# audio_amp.net
KiCad netlist of a schematic drawn in Altium Designer
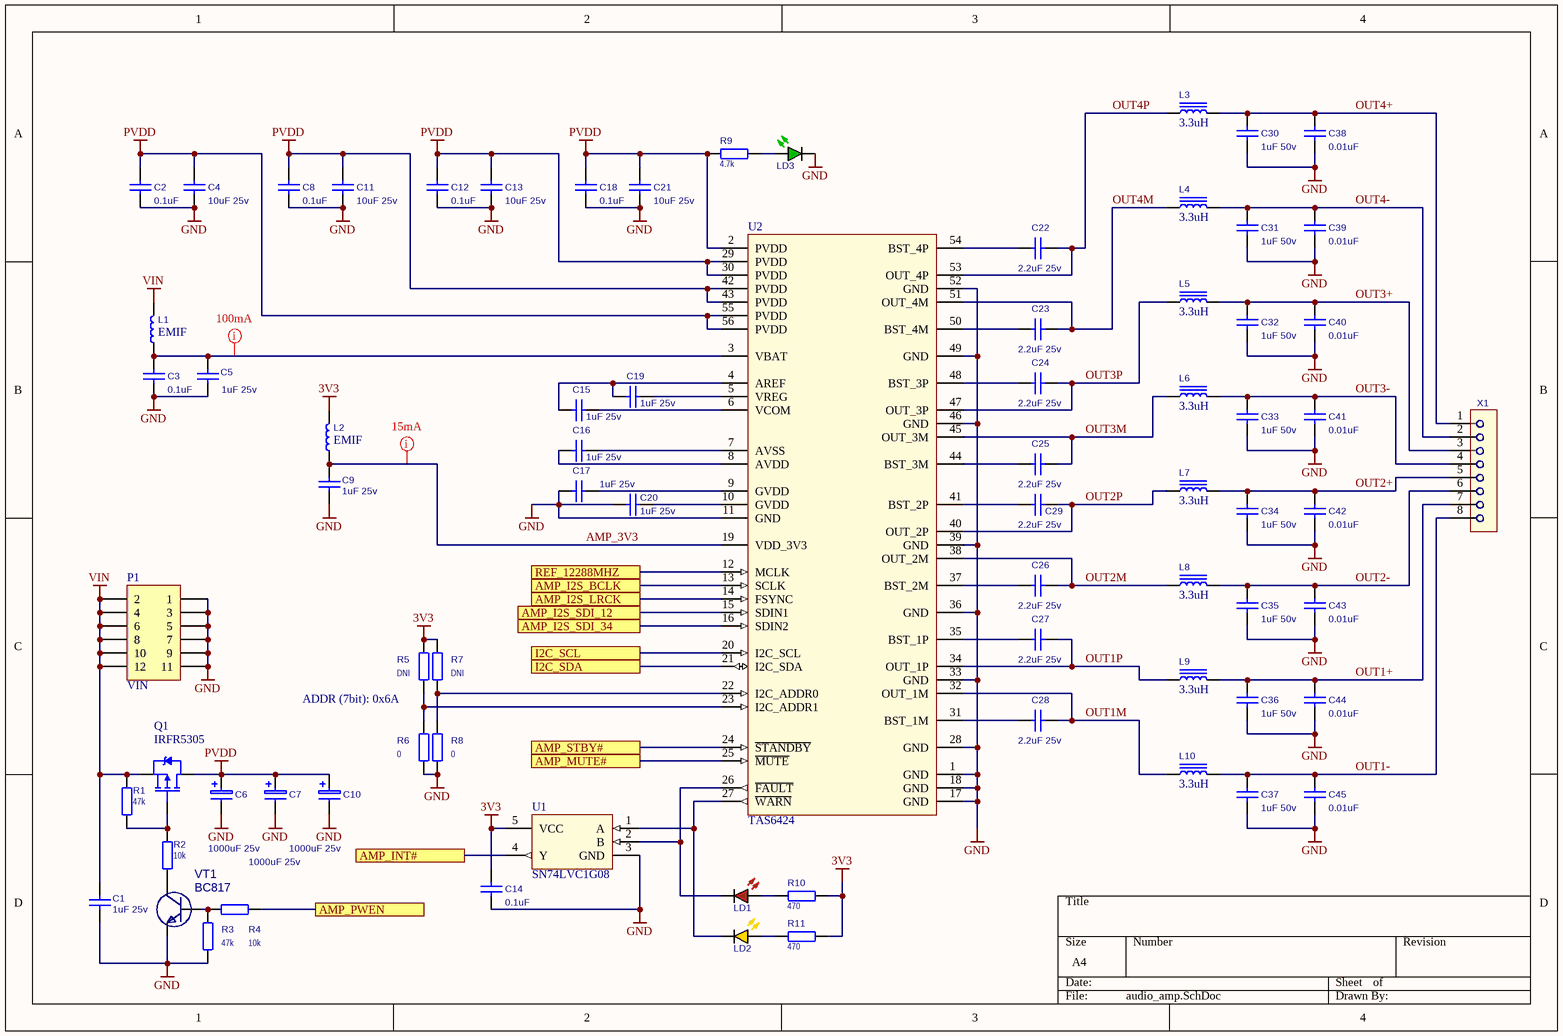
[diagram p0: audio_amp.SchDoc]

(export (version "E")
  (design (tool "Eeschema 10.0.6"))
  (components
    (comp (ref "C1")
      (value "1uF 25v")
      (footprint "Capacitors:C0603")
      (description "CAP_NPOL")
      (fields (field (name "Comment") "GRM188R61E105KA12D"))
      (libsource (lib "capacitors") (part "CAP_NPOL"))
    )
    (comp (ref "C2")
      (value "0.1uF")
      (footprint "Capacitors:C0603")
      (description "CAP_NPOL")
      (fields (field (name "Comment") "CC0603KRX7R9BB104"))
      (libsource (lib "capacitors") (part "CAP_NPOL"))
    )
    (comp (ref "C3")
      (value "0.1uF")
      (footprint "Capacitors:C0603")
      (description "CAP_NPOL")
      (fields (field (name "Comment") "CC0603KRX7R9BB104"))
      (libsource (lib "capacitors") (part "CAP_NPOL"))
    )
    (comp (ref "C4")
      (value "10uF 25v")
      (footprint "Capacitors:C0805")
      (description "CAP_NPOL")
      (fields (field (name "Comment") "GRM21BR61E106KA73L"))
      (libsource (lib "capacitors") (part "CAP_NPOL"))
    )
    (comp (ref "C5")
      (value "1uF 25v")
      (footprint "Capacitors:C0603")
      (description "CAP_NPOL")
      (fields (field (name "Comment") "GRM188R61E105KA12D"))
      (libsource (lib "capacitors") (part "CAP_NPOL"))
    )
    (comp (ref "C6")
      (value "1000uF 25v")
      (footprint "R12H05")
      (description "CAP_POL")
      (fields (field (name "Comment") "EEUFM1E102"))
      (libsource (lib "capacitors") (part "CAP_POL"))
    )
    (comp (ref "C7")
      (value "1000uF 25v")
      (footprint "R12H05")
      (description "CAP_POL")
      (fields (field (name "Comment") "EEUFM1E102"))
      (libsource (lib "capacitors") (part "CAP_POL"))
    )
    (comp (ref "C8")
      (value "0.1uF")
      (footprint "Capacitors:C0603")
      (description "CAP_NPOL")
      (fields (field (name "Comment") "CC0603KRX7R9BB104"))
      (libsource (lib "capacitors") (part "CAP_NPOL"))
    )
    (comp (ref "C9")
      (value "1uF 25v")
      (footprint "Capacitors:C0603")
      (description "CAP_NPOL")
      (fields (field (name "Comment") "GRM188R61E105KA12D"))
      (libsource (lib "capacitors") (part "CAP_NPOL"))
    )
    (comp (ref "C10")
      (value "1000uF 25v")
      (footprint "R12H05")
      (description "CAP_POL")
      (fields (field (name "Comment") "EEUFM1E102"))
      (libsource (lib "capacitors") (part "CAP_POL"))
    )
    (comp (ref "C11")
      (value "10uF 25v")
      (footprint "Capacitors:C0805")
      (description "CAP_NPOL")
      (fields (field (name "Comment") "GRM21BR61E106KA73L"))
      (libsource (lib "capacitors") (part "CAP_NPOL"))
    )
    (comp (ref "C12")
      (value "0.1uF")
      (footprint "Capacitors:C0603")
      (description "CAP_NPOL")
      (fields (field (name "Comment") "CC0603KRX7R9BB104"))
      (libsource (lib "capacitors") (part "CAP_NPOL"))
    )
    (comp (ref "C13")
      (value "10uF 25v")
      (footprint "Capacitors:C0805")
      (description "CAP_NPOL")
      (fields (field (name "Comment") "GRM21BR61E106KA73L"))
      (libsource (lib "capacitors") (part "CAP_NPOL"))
    )
    (comp (ref "C14")
      (value "0.1uF")
      (footprint "Capacitors:C0603")
      (description "CAP_NPOL")
      (fields (field (name "Comment") "CC0603KRX7R9BB104"))
      (libsource (lib "capacitors") (part "CAP_NPOL"))
    )
    (comp (ref "C15")
      (value "1uF 25v")
      (footprint "Capacitors:C0603")
      (description "CAP_NPOL")
      (fields (field (name "Comment") "GRM188R61E105KA12D"))
      (libsource (lib "capacitors") (part "CAP_NPOL"))
    )
    (comp (ref "C16")
      (value "1uF 25v")
      (footprint "Capacitors:C0603")
      (description "CAP_NPOL")
      (fields (field (name "Comment") "GRM188R61E105KA12D"))
      (libsource (lib "capacitors") (part "CAP_NPOL"))
    )
    (comp (ref "C17")
      (value "1uF 25v")
      (footprint "Capacitors:C0603")
      (description "CAP_NPOL")
      (fields (field (name "Comment") "GRM188R61E105KA12D"))
      (libsource (lib "capacitors") (part "CAP_NPOL"))
    )
    (comp (ref "C18")
      (value "0.1uF")
      (footprint "Capacitors:C0603")
      (description "CAP_NPOL")
      (fields (field (name "Comment") "CC0603KRX7R9BB104"))
      (libsource (lib "capacitors") (part "CAP_NPOL"))
    )
    (comp (ref "C19")
      (value "1uF 25v")
      (footprint "Capacitors:C0603")
      (description "CAP_NPOL")
      (fields (field (name "Comment") "GRM188R61E105KA12D"))
      (libsource (lib "capacitors") (part "CAP_NPOL"))
    )
    (comp (ref "C20")
      (value "1uF 25v")
      (footprint "Capacitors:C0603")
      (description "CAP_NPOL")
      (fields (field (name "Comment") "GRM188R61E105KA12D"))
      (libsource (lib "capacitors") (part "CAP_NPOL"))
    )
    (comp (ref "C21")
      (value "10uF 25v")
      (footprint "Capacitors:C0805")
      (description "CAP_NPOL")
      (fields (field (name "Comment") "GRM21BR61E106KA73L"))
      (libsource (lib "capacitors") (part "CAP_NPOL"))
    )
    (comp (ref "C22")
      (value "2.2uF 25v")
      (footprint "Capacitors:C0603")
      (description "CAP_NPOL")
      (fields (field (name "Comment") "CL10A225KA8NNNC"))
      (libsource (lib "capacitors") (part "CAP_NPOL"))
    )
    (comp (ref "C23")
      (value "2.2uF 25v")
      (footprint "Capacitors:C0603")
      (description "CAP_NPOL")
      (fields (field (name "Comment") "CL10A225KA8NNNC"))
      (libsource (lib "capacitors") (part "CAP_NPOL"))
    )
    (comp (ref "C24")
      (value "2.2uF 25v")
      (footprint "Capacitors:C0603")
      (description "CAP_NPOL")
      (fields (field (name "Comment") "CL10A225KA8NNNC"))
      (libsource (lib "capacitors") (part "CAP_NPOL"))
    )
    (comp (ref "C25")
      (value "2.2uF 25v")
      (footprint "Capacitors:C0603")
      (description "CAP_NPOL")
      (fields (field (name "Comment") "CL10A225KA8NNNC"))
      (libsource (lib "capacitors") (part "CAP_NPOL"))
    )
    (comp (ref "C26")
      (value "2.2uF 25v")
      (footprint "Capacitors:C0603")
      (description "CAP_NPOL")
      (fields (field (name "Comment") "CL10A225KA8NNNC"))
      (libsource (lib "capacitors") (part "CAP_NPOL"))
    )
    (comp (ref "C27")
      (value "2.2uF 25v")
      (footprint "Capacitors:C0603")
      (description "CAP_NPOL")
      (fields (field (name "Comment") "CL10A225KA8NNNC"))
      (libsource (lib "capacitors") (part "CAP_NPOL"))
    )
    (comp (ref "C28")
      (value "2.2uF 25v")
      (footprint "Capacitors:C0603")
      (description "CAP_NPOL")
      (fields (field (name "Comment") "CL10A225KA8NNNC"))
      (libsource (lib "capacitors") (part "CAP_NPOL"))
    )
    (comp (ref "C29")
      (value "2.2uF 25v")
      (footprint "Capacitors:C0603")
      (description "CAP_NPOL")
      (fields (field (name "Comment") "CL10A225KA8NNNC"))
      (libsource (lib "capacitors") (part "CAP_NPOL"))
    )
    (comp (ref "C30")
      (value "1uF 50v")
      (footprint "Capacitors:C0603")
      (description "CAP_NPOL")
      (fields (field (name "Comment") "CL10A105KB8NNNC"))
      (libsource (lib "capacitors") (part "CAP_NPOL"))
    )
    (comp (ref "C31")
      (value "1uF 50v")
      (footprint "Capacitors:C0603")
      (description "CAP_NPOL")
      (fields (field (name "Comment") "CL10A105KB8NNNC"))
      (libsource (lib "capacitors") (part "CAP_NPOL"))
    )
    (comp (ref "C32")
      (value "1uF 50v")
      (footprint "Capacitors:C0603")
      (description "CAP_NPOL")
      (fields (field (name "Comment") "CL10A105KB8NNNC"))
      (libsource (lib "capacitors") (part "CAP_NPOL"))
    )
    (comp (ref "C33")
      (value "1uF 50v")
      (footprint "Capacitors:C0603")
      (description "CAP_NPOL")
      (fields (field (name "Comment") "CL10A105KB8NNNC"))
      (libsource (lib "capacitors") (part "CAP_NPOL"))
    )
    (comp (ref "C34")
      (value "1uF 50v")
      (footprint "Capacitors:C0603")
      (description "CAP_NPOL")
      (fields (field (name "Comment") "CL10A105KB8NNNC"))
      (libsource (lib "capacitors") (part "CAP_NPOL"))
    )
    (comp (ref "C35")
      (value "1uF 50v")
      (footprint "Capacitors:C0603")
      (description "CAP_NPOL")
      (fields (field (name "Comment") "CL10A105KB8NNNC"))
      (libsource (lib "capacitors") (part "CAP_NPOL"))
    )
    (comp (ref "C36")
      (value "1uF 50v")
      (footprint "Capacitors:C0603")
      (description "CAP_NPOL")
      (fields (field (name "Comment") "CL10A105KB8NNNC"))
      (libsource (lib "capacitors") (part "CAP_NPOL"))
    )
    (comp (ref "C37")
      (value "1uF 50v")
      (footprint "Capacitors:C0603")
      (description "CAP_NPOL")
      (fields (field (name "Comment") "CL10A105KB8NNNC"))
      (libsource (lib "capacitors") (part "CAP_NPOL"))
    )
    (comp (ref "C38")
      (value "0.01uF")
      (footprint "Capacitors:C0603")
      (description "CAP_NPOL")
      (fields (field (name "Comment") "CL10B103KB8NNNC"))
      (libsource (lib "capacitors") (part "CAP_NPOL"))
    )
    (comp (ref "C39")
      (value "0.01uF")
      (footprint "Capacitors:C0603")
      (description "CAP_NPOL")
      (fields (field (name "Comment") "CL10B103KB8NNNC"))
      (libsource (lib "capacitors") (part "CAP_NPOL"))
    )
    (comp (ref "C40")
      (value "0.01uF")
      (footprint "Capacitors:C0603")
      (description "CAP_NPOL")
      (fields (field (name "Comment") "CL10B103KB8NNNC"))
      (libsource (lib "capacitors") (part "CAP_NPOL"))
    )
    (comp (ref "C41")
      (value "0.01uF")
      (footprint "Capacitors:C0603")
      (description "CAP_NPOL")
      (fields (field (name "Comment") "CL10B103KB8NNNC"))
      (libsource (lib "capacitors") (part "CAP_NPOL"))
    )
    (comp (ref "C42")
      (value "0.01uF")
      (footprint "Capacitors:C0603")
      (description "CAP_NPOL")
      (fields (field (name "Comment") "CL10B103KB8NNNC"))
      (libsource (lib "capacitors") (part "CAP_NPOL"))
    )
    (comp (ref "C43")
      (value "0.01uF")
      (footprint "Capacitors:C0603")
      (description "CAP_NPOL")
      (fields (field (name "Comment") "CL10B103KB8NNNC"))
      (libsource (lib "capacitors") (part "CAP_NPOL"))
    )
    (comp (ref "C44")
      (value "0.01uF")
      (footprint "Capacitors:C0603")
      (description "CAP_NPOL")
      (fields (field (name "Comment") "CL10B103KB8NNNC"))
      (libsource (lib "capacitors") (part "CAP_NPOL"))
    )
    (comp (ref "C45")
      (value "0.01uF")
      (footprint "Capacitors:C0603")
      (description "CAP_NPOL")
      (fields (field (name "Comment") "CL10B103KB8NNNC"))
      (libsource (lib "capacitors") (part "CAP_NPOL"))
    )
    (comp (ref "L1")
      (value "EMIF")
      (footprint "IND0603")
      (description "IND_WO_IRON")
      (fields (field (name "Comment") "BLM18AG102SN1D"))
      (libsource (lib "inductors") (part "IND_WO_IRON"))
    )
    (comp (ref "L2")
      (value "EMIF")
      (footprint "IND0603")
      (description "IND_WO_IRON")
      (fields (field (name "Comment") "BLM18AG102SN1D"))
      (libsource (lib "inductors") (part "IND_WO_IRON"))
    )
    (comp (ref "L3")
      (value "3.3uH")
      (footprint "IHLP-2525CZ")
      (description "IND_W_IRON")
      (fields (field (name "Comment") "IHLP2525CZER3R3M01"))
      (libsource (lib "inductors") (part "IND_W_IRON"))
    )
    (comp (ref "L4")
      (value "3.3uH")
      (footprint "IHLP-2525CZ")
      (description "IND_W_IRON")
      (fields (field (name "Comment") "IHLP2525CZER3R3M01"))
      (libsource (lib "") (part "IND_W_IRON_1"))
    )
    (comp (ref "L5")
      (value "3.3uH")
      (footprint "IHLP-2525CZ")
      (description "IND_W_IRON")
      (fields (field (name "Comment") "IHLP2525CZER3R3M01"))
      (libsource (lib "inductors") (part "IND_W_IRON"))
    )
    (comp (ref "L6")
      (value "3.3uH")
      (footprint "IHLP-2525CZ")
      (description "IND_W_IRON")
      (fields (field (name "Comment") "IHLP2525CZER3R3M01"))
      (libsource (lib "inductors") (part "IND_W_IRON"))
    )
    (comp (ref "L7")
      (value "3.3uH")
      (footprint "IHLP-2525CZ")
      (description "IND_W_IRON")
      (fields (field (name "Comment") "IHLP2525CZER3R3M01"))
      (libsource (lib "inductors") (part "IND_W_IRON"))
    )
    (comp (ref "L8")
      (value "3.3uH")
      (footprint "IHLP-2525CZ")
      (description "IND_W_IRON")
      (fields (field (name "Comment") "IHLP2525CZER3R3M01"))
      (libsource (lib "inductors") (part "IND_W_IRON"))
    )
    (comp (ref "L9")
      (value "3.3uH")
      (footprint "IHLP-2525CZ")
      (description "IND_W_IRON")
      (fields (field (name "Comment") "IHLP2525CZER3R3M01"))
      (libsource (lib "inductors") (part "IND_W_IRON"))
    )
    (comp (ref "L10")
      (value "3.3uH")
      (footprint "IHLP-2525CZ")
      (description "IND_W_IRON")
      (fields (field (name "Comment") "IHLP2525CZER3R3M01"))
      (libsource (lib "inductors") (part "IND_W_IRON"))
    )
    (comp (ref "LD1")
      (value "LED_R")
      (footprint "Resistors:R0603")
      (description "LED Red")
      (libsource (lib "leds") (part "LED_RED"))
    )
    (comp (ref "LD2")
      (value "LED_Y")
      (footprint "Resistors:R0603")
      (description "LED Yellow")
      (libsource (lib "leds") (part "LED_YELLOW"))
    )
    (comp (ref "LD3")
      (value "LED_G")
      (footprint "Resistors:R0603")
      (description "LED Green")
      (libsource (lib "leds") (part "LED_GREEN"))
    )
    (comp (ref "P1")
      (value "VIN")
      (footprint "PLD-6")
      (description "Header, 6-Pin, Dual row")
      (fields (field (name "PUBLISHER") "Altium Limited"))
      (libsource (lib "HDR") (part "HDR 6X2"))
    )
    (comp (ref "Q1")
      (value "IRFR5305")
      (footprint "D-PAK")
      (description "HEXFET Power MOSFET")
      (libsource (lib "MOSFET") (part "P-Channel"))
    )
    (comp (ref "R1")
      (value "47k")
      (footprint "Resistors:R0603")
      (description "RES")
      (libsource (lib "resistors") (part "RESISTOR"))
    )
    (comp (ref "R2")
      (value "10k")
      (footprint "Resistors:R0603")
      (description "RES")
      (libsource (lib "resistors") (part "RESISTOR"))
    )
    (comp (ref "R3")
      (value "47k")
      (footprint "Resistors:R0603")
      (description "RES")
      (libsource (lib "resistors") (part "RESISTOR"))
    )
    (comp (ref "R4")
      (value "10k")
      (footprint "Resistors:R0603")
      (description "RES")
      (libsource (lib "resistors") (part "RESISTOR"))
    )
    (comp (ref "R5")
      (value "DNI")
      (footprint "R0603")
      (description "RES")
      (fields (field (name "Comment") "47k"))
      (libsource (lib "resistors") (part "RESISTOR"))
    )
    (comp (ref "R6")
      (value "0")
      (footprint "R0603")
      (description "RES")
      (fields (field (name "Comment") "47k"))
      (libsource (lib "resistors") (part "RESISTOR"))
    )
    (comp (ref "R7")
      (value "DNI")
      (footprint "R0603")
      (description "RES")
      (fields (field (name "Comment") "47k"))
      (libsource (lib "resistors") (part "RESISTOR"))
    )
    (comp (ref "R8")
      (value "0")
      (footprint "R0603")
      (description "RES")
      (fields (field (name "Comment") "47k"))
      (libsource (lib "resistors") (part "RESISTOR"))
    )
    (comp (ref "R9")
      (value "4.7k")
      (footprint "Resistors:R0603")
      (description "RES")
      (libsource (lib "resistors") (part "RESISTOR"))
    )
    (comp (ref "R10")
      (value "470")
      (footprint "R0603")
      (description "RES")
      (libsource (lib "resistors") (part "RESISTOR"))
    )
    (comp (ref "R11")
      (value "470")
      (footprint "R0603")
      (description "RES")
      (libsource (lib "resistors") (part "RESISTOR"))
    )
    (comp (ref "U1")
      (value "SN74LVC1G08")
      (footprint "SOT-23-5")
      (fields (field (name "Comment") "SN74LVC1G08DBVR"))
      (libsource (lib "SN74LVC1G08") (part "SN74LVC1G08"))
    )
    (comp (ref "U2") (value "TAS6424") (footprint "HSSOP-56") (libsource (lib "TAS6424") (part "TAS6424")))
    (comp (ref "VT1")
      (value "BC817")
      (footprint "SOT-23-3")
      (description "Bipolar transistor N-P-N")
      (libsource (lib "BIPOLAR") (part "N-P-N"))
    )
    (comp (ref "X1")
      (value "DGxxx-8")
      (footprint "DG126-5.0-8P")
      (description "PCB terminal block")
      (libsource (lib "DGxxx") (part "DGxxx-8"))
    )
  )
  (nets
    (net (code "1") (name "/AMP_3V3") (class "Default")
      (node (ref "C9") (pin "2") (pinfunction "2_2") (pintype "passive"))
      (node (ref "L2") (pin "1") (pintype "passive"))
      (node (ref "U2") (pin "19") (pinfunction "VDD_3V3_19") (pintype "power_in"))
    )
    (net (code "2") (name "/AMP_I2S_BCLK") (class "Default")
      (node (ref "U2") (pin "13") (pinfunction "SCLK_13") (pintype "input"))
    )
    (net (code "3") (name "/AMP_I2S_LRCK") (class "Default")
      (node (ref "U2") (pin "14") (pinfunction "FSYNC_14") (pintype "input"))
    )
    (net (code "4") (name "/AMP_I2S_SDI_12") (class "Default")
      (node (ref "U2") (pin "15") (pinfunction "SDIN1_15") (pintype "input"))
    )
    (net (code "5") (name "/AMP_I2S_SDI_34") (class "Default")
      (node (ref "U2") (pin "16") (pinfunction "SDIN2_16") (pintype "input"))
    )
    (net (code "6") (name "/AMP_INT#") (class "Default")
      (node (ref "U1") (pin "4") (pinfunction "Y_4") (pintype "output"))
    )
    (net (code "7") (name "/AMP_MUTE#") (class "Default")
      (node (ref "U2") (pin "25") (pinfunction "~{MUTE}_25") (pintype "input"))
    )
    (net (code "8") (name "/AMP_PWEN") (class "Default")
      (node (ref "R4") (pin "1") (pinfunction "1_1") (pintype "passive"))
    )
    (net (code "9") (name "/AMP_STBY#") (class "Default")
      (node (ref "U2") (pin "24") (pinfunction "~{STANDBY}_24") (pintype "input"))
    )
    (net (code "10") (name "/I2C_SCL") (class "Default")
      (node (ref "U2") (pin "20") (pinfunction "I2C_SCL_20") (pintype "input"))
    )
    (net (code "11") (name "/I2C_SDA") (class "Default")
      (node (ref "U2") (pin "21") (pinfunction "I2C_SDA_21") (pintype "bidirectional"))
    )
    (net (code "12") (name "/OUT1+") (class "Default")
      (node (ref "C36") (pin "1") (pinfunction "1_1") (pintype "passive"))
      (node (ref "C44") (pin "1") (pinfunction "1_1") (pintype "passive"))
      (node (ref "L9") (pin "2") (pintype "passive"))
      (node (ref "X1") (pin "7") (pinfunction "7_7") (pintype "passive"))
    )
    (net (code "13") (name "/OUT1-") (class "Default")
      (node (ref "C37") (pin "1") (pinfunction "1_1") (pintype "passive"))
      (node (ref "C45") (pin "1") (pinfunction "1_1") (pintype "passive"))
      (node (ref "L10") (pin "2") (pintype "passive"))
      (node (ref "X1") (pin "8") (pinfunction "8_8") (pintype "passive"))
    )
    (net (code "14") (name "/OUT1M") (class "Default")
      (node (ref "C28") (pin "1") (pinfunction "1_1") (pintype "passive"))
      (node (ref "L10") (pin "1") (pintype "passive"))
      (node (ref "U2") (pin "32") (pinfunction "OUT_1M_32") (pintype "passive"))
    )
    (net (code "15") (name "/OUT1P") (class "Default")
      (node (ref "C27") (pin "1") (pinfunction "1_1") (pintype "passive"))
      (node (ref "L9") (pin "1") (pintype "passive"))
      (node (ref "U2") (pin "34") (pinfunction "OUT_1P_34") (pintype "passive"))
    )
    (net (code "16") (name "/OUT2+") (class "Default")
      (node (ref "C34") (pin "1") (pinfunction "1_1") (pintype "passive"))
      (node (ref "C42") (pin "1") (pinfunction "1_1") (pintype "passive"))
      (node (ref "L7") (pin "2") (pintype "passive"))
      (node (ref "X1") (pin "5") (pinfunction "5_5") (pintype "passive"))
    )
    (net (code "17") (name "/OUT2-") (class "Default")
      (node (ref "C35") (pin "1") (pinfunction "1_1") (pintype "passive"))
      (node (ref "C43") (pin "1") (pinfunction "1_1") (pintype "passive"))
      (node (ref "L8") (pin "2") (pintype "passive"))
      (node (ref "X1") (pin "6") (pinfunction "6_6") (pintype "passive"))
    )
    (net (code "18") (name "/OUT2M") (class "Default")
      (node (ref "C26") (pin "1") (pinfunction "1_1") (pintype "passive"))
      (node (ref "L8") (pin "1") (pintype "passive"))
      (node (ref "U2") (pin "38") (pinfunction "OUT_2M_38") (pintype "passive"))
    )
    (net (code "19") (name "/OUT2P") (class "Default")
      (node (ref "C29") (pin "1") (pinfunction "1_1") (pintype "passive"))
      (node (ref "L7") (pin "1") (pintype "passive"))
      (node (ref "U2") (pin "40") (pinfunction "OUT_2P_40") (pintype "passive"))
    )
    (net (code "20") (name "/OUT3+") (class "Default")
      (node (ref "C32") (pin "1") (pinfunction "1_1") (pintype "passive"))
      (node (ref "C40") (pin "1") (pinfunction "1_1") (pintype "passive"))
      (node (ref "L5") (pin "2") (pintype "passive"))
      (node (ref "X1") (pin "3") (pinfunction "3_3") (pintype "passive"))
    )
    (net (code "21") (name "/OUT3-") (class "Default")
      (node (ref "C33") (pin "1") (pinfunction "1_1") (pintype "passive"))
      (node (ref "C41") (pin "1") (pinfunction "1_1") (pintype "passive"))
      (node (ref "L6") (pin "2") (pintype "passive"))
      (node (ref "X1") (pin "4") (pinfunction "4_4") (pintype "passive"))
    )
    (net (code "22") (name "/OUT3M") (class "Default")
      (node (ref "C25") (pin "1") (pinfunction "1_1") (pintype "passive"))
      (node (ref "L6") (pin "1") (pintype "passive"))
      (node (ref "U2") (pin "45") (pinfunction "OUT_3M_45") (pintype "passive"))
    )
    (net (code "23") (name "/OUT3P") (class "Default")
      (node (ref "C24") (pin "1") (pinfunction "1_1") (pintype "passive"))
      (node (ref "L5") (pin "1") (pintype "passive"))
      (node (ref "U2") (pin "47") (pinfunction "OUT_3P_47") (pintype "passive"))
    )
    (net (code "24") (name "/OUT4+") (class "Default")
      (node (ref "C30") (pin "1") (pinfunction "1_1") (pintype "passive"))
      (node (ref "C38") (pin "1") (pinfunction "1_1") (pintype "passive"))
      (node (ref "L3") (pin "2") (pintype "passive"))
      (node (ref "X1") (pin "1") (pinfunction "1_1") (pintype "passive"))
    )
    (net (code "25") (name "/OUT4-") (class "Default")
      (node (ref "C31") (pin "1") (pinfunction "1_1") (pintype "passive"))
      (node (ref "C39") (pin "1") (pinfunction "1_1") (pintype "passive"))
      (node (ref "L4") (pin "1") (pintype "passive"))
      (node (ref "X1") (pin "2") (pinfunction "2_2") (pintype "passive"))
    )
    (net (code "26") (name "/OUT4M") (class "Default")
      (node (ref "C23") (pin "1") (pinfunction "1_1") (pintype "passive"))
      (node (ref "L4") (pin "2") (pintype "passive"))
      (node (ref "U2") (pin "51") (pinfunction "OUT_4M_51") (pintype "passive"))
    )
    (net (code "27") (name "/OUT4P") (class "Default")
      (node (ref "C22") (pin "1") (pinfunction "1_1") (pintype "passive"))
      (node (ref "L3") (pin "1") (pintype "passive"))
      (node (ref "U2") (pin "53") (pinfunction "OUT_4P_53") (pintype "passive"))
    )
    (net (code "28") (name "/REF_12288MHZ") (class "Default")
      (node (ref "U2") (pin "12") (pinfunction "MCLK_12") (pintype "input"))
    )
    (net (code "29") (name "3V3") (class "Default")
      (node (ref "C14") (pin "1") (pinfunction "1_1") (pintype "passive"))
      (node (ref "L2") (pin "2") (pintype "passive"))
      (node (ref "R10") (pin "1") (pinfunction "1_1") (pintype "passive"))
      (node (ref "R11") (pin "1") (pinfunction "1_1") (pintype "passive"))
      (node (ref "R5") (pin "1") (pinfunction "1_1") (pintype "passive"))
      (node (ref "R7") (pin "1") (pinfunction "1_1") (pintype "passive"))
      (node (ref "U1") (pin "5") (pinfunction "VCC_5") (pintype "power_in"))
    )
    (net (code "30") (name "GND") (class "Default")
      (node (ref "C1") (pin "1") (pinfunction "1_1") (pintype "passive"))
      (node (ref "C10") (pin "2") (pinfunction "-_2") (pintype "passive"))
      (node (ref "C11") (pin "2") (pinfunction "2_2") (pintype "passive"))
      (node (ref "C12") (pin "2") (pinfunction "2_2") (pintype "passive"))
      (node (ref "C13") (pin "2") (pinfunction "2_2") (pintype "passive"))
      (node (ref "C14") (pin "2") (pinfunction "2_2") (pintype "passive"))
      (node (ref "C17") (pin "1") (pinfunction "1_1") (pintype "passive"))
      (node (ref "C18") (pin "2") (pinfunction "2_2") (pintype "passive"))
      (node (ref "C2") (pin "2") (pinfunction "2_2") (pintype "passive"))
      (node (ref "C20") (pin "1") (pinfunction "1_1") (pintype "passive"))
      (node (ref "C21") (pin "2") (pinfunction "2_2") (pintype "passive"))
      (node (ref "C3") (pin "2") (pinfunction "2_2") (pintype "passive"))
      (node (ref "C30") (pin "2") (pinfunction "2_2") (pintype "passive"))
      (node (ref "C31") (pin "2") (pinfunction "2_2") (pintype "passive"))
      (node (ref "C32") (pin "2") (pinfunction "2_2") (pintype "passive"))
      (node (ref "C33") (pin "2") (pinfunction "2_2") (pintype "passive"))
      (node (ref "C34") (pin "2") (pinfunction "2_2") (pintype "passive"))
      (node (ref "C35") (pin "2") (pinfunction "2_2") (pintype "passive"))
      (node (ref "C36") (pin "2") (pinfunction "2_2") (pintype "passive"))
      (node (ref "C37") (pin "2") (pinfunction "2_2") (pintype "passive"))
      (node (ref "C38") (pin "2") (pinfunction "2_2") (pintype "passive"))
      (node (ref "C39") (pin "2") (pinfunction "2_2") (pintype "passive"))
      (node (ref "C4") (pin "2") (pinfunction "2_2") (pintype "passive"))
      (node (ref "C40") (pin "2") (pinfunction "2_2") (pintype "passive"))
      (node (ref "C41") (pin "2") (pinfunction "2_2") (pintype "passive"))
      (node (ref "C42") (pin "2") (pinfunction "2_2") (pintype "passive"))
      (node (ref "C43") (pin "2") (pinfunction "2_2") (pintype "passive"))
      (node (ref "C44") (pin "2") (pinfunction "2_2") (pintype "passive"))
      (node (ref "C45") (pin "2") (pinfunction "2_2") (pintype "passive"))
      (node (ref "C5") (pin "1") (pinfunction "1_1") (pintype "passive"))
      (node (ref "C6") (pin "2") (pinfunction "-_2") (pintype "passive"))
      (node (ref "C7") (pin "2") (pinfunction "-_2") (pintype "passive"))
      (node (ref "C8") (pin "2") (pinfunction "2_2") (pintype "passive"))
      (node (ref "C9") (pin "1") (pinfunction "1_1") (pintype "passive"))
      (node (ref "LD3") (pin "1") (pintype "passive"))
      (node (ref "P1") (pin "1") (pinfunction "1_1") (pintype "passive"))
      (node (ref "P1") (pin "11") (pinfunction "11_11") (pintype "passive"))
      (node (ref "P1") (pin "3") (pinfunction "3_3") (pintype "passive"))
      (node (ref "P1") (pin "5") (pinfunction "5_5") (pintype "passive"))
      (node (ref "P1") (pin "7") (pinfunction "7_7") (pintype "passive"))
      (node (ref "P1") (pin "9") (pinfunction "9_9") (pintype "passive"))
      (node (ref "R3") (pin "1") (pinfunction "1_1") (pintype "passive"))
      (node (ref "R6") (pin "2") (pinfunction "2_2") (pintype "passive"))
      (node (ref "R8") (pin "2") (pinfunction "2_2") (pintype "passive"))
      (node (ref "U1") (pin "3") (pinfunction "GND_3") (pintype "power_in"))
      (node (ref "U2") (pin "1") (pinfunction "GND_1") (pintype "power_in"))
      (node (ref "U2") (pin "11") (pinfunction "GND_11") (pintype "power_in"))
      (node (ref "U2") (pin "17") (pinfunction "GND_17") (pintype "power_in"))
      (node (ref "U2") (pin "18") (pinfunction "GND_18") (pintype "power_in"))
      (node (ref "U2") (pin "28") (pinfunction "GND_28") (pintype "power_in"))
      (node (ref "U2") (pin "33") (pinfunction "GND_33") (pintype "power_in"))
      (node (ref "U2") (pin "36") (pinfunction "GND_36") (pintype "power_in"))
      (node (ref "U2") (pin "39") (pinfunction "GND_39") (pintype "power_in"))
      (node (ref "U2") (pin "46") (pinfunction "GND_46") (pintype "power_in"))
      (node (ref "U2") (pin "49") (pinfunction "GND_49") (pintype "power_in"))
      (node (ref "U2") (pin "52") (pinfunction "GND_52") (pintype "power_in"))
      (node (ref "VT1") (pin "2") (pintype "passive"))
    )
    (net (code "31") (name "Net-(C17-Pad2)") (class "Default")
      (node (ref "C17") (pin "2") (pinfunction "2_2") (pintype "passive"))
      (node (ref "U2") (pin "9") (pinfunction "GVDD_9") (pintype "power_in"))
    )
    (net (code "32") (name "Net-(C20-Pad2)") (class "Default")
      (node (ref "C20") (pin "2") (pinfunction "2_2") (pintype "passive"))
      (node (ref "U2") (pin "10") (pinfunction "GVDD_10") (pintype "power_in"))
    )
    (net (code "33") (name "Net-(LD1-Pad2)") (class "Default")
      (node (ref "LD1") (pin "2") (pintype "passive"))
      (node (ref "R10") (pin "2") (pinfunction "2_2") (pintype "passive"))
    )
    (net (code "34") (name "Net-(LD2-Pad2)") (class "Default")
      (node (ref "LD2") (pin "2") (pintype "passive"))
      (node (ref "R11") (pin "2") (pinfunction "2_2") (pintype "passive"))
    )
    (net (code "35") (name "Net-(LD3-Pad2)") (class "Default")
      (node (ref "LD3") (pin "2") (pintype "passive"))
      (node (ref "R9") (pin "2") (pinfunction "2_2") (pintype "passive"))
    )
    (net (code "36") (name "Net-(Q1-G)") (class "Default")
      (node (ref "Q1") (pin "1") (pinfunction "G_1") (pintype "passive"))
      (node (ref "R1") (pin "2") (pinfunction "2_2") (pintype "passive"))
      (node (ref "R2") (pin "2") (pinfunction "2_2") (pintype "passive"))
    )
    (net (code "37") (name "Net-(R2-Pad1)") (class "Default")
      (node (ref "R2") (pin "1") (pinfunction "1_1") (pintype "passive"))
      (node (ref "VT1") (pin "3") (pintype "passive"))
    )
    (net (code "38") (name "Net-(R3-Pad2)") (class "Default")
      (node (ref "R3") (pin "2") (pinfunction "2_2") (pintype "passive"))
      (node (ref "R4") (pin "2") (pinfunction "2_2") (pintype "passive"))
      (node (ref "VT1") (pin "1") (pintype "passive"))
    )
    (net (code "39") (name "Net-(U1-A)") (class "Default")
      (node (ref "LD2") (pin "1") (pintype "passive"))
      (node (ref "U1") (pin "1") (pinfunction "A_1") (pintype "input"))
      (node (ref "U2") (pin "27") (pinfunction "~{WARN}_27") (pintype "output"))
    )
    (net (code "40") (name "Net-(U1-B)") (class "Default")
      (node (ref "LD1") (pin "1") (pintype "passive"))
      (node (ref "U1") (pin "2") (pinfunction "B_2") (pintype "input"))
      (node (ref "U2") (pin "26") (pinfunction "~{FAULT}_26") (pintype "output"))
    )
    (net (code "41") (name "Net-(U2-AREF)") (class "Default")
      (node (ref "C15") (pin "2") (pinfunction "2_2") (pintype "passive"))
      (node (ref "C19") (pin "2") (pinfunction "2_2") (pintype "passive"))
      (node (ref "U2") (pin "4") (pinfunction "AREF_4") (pintype "power_in"))
    )
    (net (code "42") (name "Net-(U2-AVDD)") (class "Default")
      (node (ref "C16") (pin "1") (pinfunction "1_1") (pintype "passive"))
      (node (ref "U2") (pin "8") (pinfunction "AVDD_8") (pintype "power_in"))
    )
    (net (code "43") (name "Net-(U2-AVSS)") (class "Default")
      (node (ref "C16") (pin "2") (pinfunction "2_2") (pintype "passive"))
      (node (ref "U2") (pin "7") (pinfunction "AVSS_7") (pintype "power_in"))
    )
    (net (code "44") (name "Net-(U2-BST_1M)") (class "Default")
      (node (ref "C28") (pin "2") (pinfunction "2_2") (pintype "passive"))
      (node (ref "U2") (pin "31") (pinfunction "BST_1M_31") (pintype "power_in"))
    )
    (net (code "45") (name "Net-(U2-BST_1P)") (class "Default")
      (node (ref "C27") (pin "2") (pinfunction "2_2") (pintype "passive"))
      (node (ref "U2") (pin "35") (pinfunction "BST_1P_35") (pintype "power_in"))
    )
    (net (code "46") (name "Net-(U2-BST_2M)") (class "Default")
      (node (ref "C26") (pin "2") (pinfunction "2_2") (pintype "passive"))
      (node (ref "U2") (pin "37") (pinfunction "BST_2M_37") (pintype "power_in"))
    )
    (net (code "47") (name "Net-(U2-BST_2P)") (class "Default")
      (node (ref "C29") (pin "2") (pinfunction "2_2") (pintype "passive"))
      (node (ref "U2") (pin "41") (pinfunction "BST_2P_41") (pintype "power_in"))
    )
    (net (code "48") (name "Net-(U2-BST_3M)") (class "Default")
      (node (ref "C25") (pin "2") (pinfunction "2_2") (pintype "passive"))
      (node (ref "U2") (pin "44") (pinfunction "BST_3M_44") (pintype "power_in"))
    )
    (net (code "49") (name "Net-(U2-BST_3P)") (class "Default")
      (node (ref "C24") (pin "2") (pinfunction "2_2") (pintype "passive"))
      (node (ref "U2") (pin "48") (pinfunction "BST_3P_48") (pintype "power_in"))
    )
    (net (code "50") (name "Net-(U2-BST_4M)") (class "Default")
      (node (ref "C23") (pin "2") (pinfunction "2_2") (pintype "passive"))
      (node (ref "U2") (pin "50") (pinfunction "BST_4M_50") (pintype "power_in"))
    )
    (net (code "51") (name "Net-(U2-BST_4P)") (class "Default")
      (node (ref "C22") (pin "2") (pinfunction "2_2") (pintype "passive"))
      (node (ref "U2") (pin "54") (pinfunction "BST_4P_54") (pintype "power_in"))
    )
    (net (code "52") (name "Net-(U2-I2C_ADDR0)") (class "Default")
      (node (ref "R7") (pin "2") (pinfunction "2_2") (pintype "passive"))
      (node (ref "R8") (pin "1") (pinfunction "1_1") (pintype "passive"))
      (node (ref "U2") (pin "22") (pinfunction "I2C_ADDR0_22") (pintype "input"))
    )
    (net (code "53") (name "Net-(U2-I2C_ADDR1)") (class "Default")
      (node (ref "R5") (pin "2") (pinfunction "2_2") (pintype "passive"))
      (node (ref "R6") (pin "1") (pinfunction "1_1") (pintype "passive"))
      (node (ref "U2") (pin "23") (pinfunction "I2C_ADDR1_23") (pintype "input"))
    )
    (net (code "54") (name "Net-(U2-VBAT)") (class "Default")
      (node (ref "C3") (pin "1") (pinfunction "1_1") (pintype "passive"))
      (node (ref "C5") (pin "2") (pinfunction "2_2") (pintype "passive"))
      (node (ref "L1") (pin "1") (pintype "passive"))
      (node (ref "U2") (pin "3") (pinfunction "VBAT_3") (pintype "power_in"))
    )
    (net (code "55") (name "Net-(U2-VCOM)") (class "Default")
      (node (ref "C15") (pin "1") (pinfunction "1_1") (pintype "passive"))
      (node (ref "U2") (pin "6") (pinfunction "VCOM_6") (pintype "power_in"))
    )
    (net (code "56") (name "Net-(U2-VREG)") (class "Default")
      (node (ref "C19") (pin "1") (pinfunction "1_1") (pintype "passive"))
      (node (ref "U2") (pin "5") (pinfunction "VREG_5") (pintype "power_in"))
    )
    (net (code "57") (name "PVDD") (class "Default")
      (node (ref "C10") (pin "1") (pinfunction "+_1") (pintype "passive"))
      (node (ref "C11") (pin "1") (pinfunction "1_1") (pintype "passive"))
      (node (ref "C12") (pin "1") (pinfunction "1_1") (pintype "passive"))
      (node (ref "C13") (pin "1") (pinfunction "1_1") (pintype "passive"))
      (node (ref "C18") (pin "1") (pinfunction "1_1") (pintype "passive"))
      (node (ref "C2") (pin "1") (pinfunction "1_1") (pintype "passive"))
      (node (ref "C21") (pin "1") (pinfunction "1_1") (pintype "passive"))
      (node (ref "C4") (pin "1") (pinfunction "1_1") (pintype "passive"))
      (node (ref "C6") (pin "1") (pinfunction "+_1") (pintype "passive"))
      (node (ref "C7") (pin "1") (pinfunction "+_1") (pintype "passive"))
      (node (ref "C8") (pin "1") (pinfunction "1_1") (pintype "passive"))
      (node (ref "Q1") (pin "2") (pinfunction "D_2") (pintype "passive"))
      (node (ref "R9") (pin "1") (pinfunction "1_1") (pintype "passive"))
      (node (ref "U2") (pin "2") (pinfunction "PVDD_2") (pintype "power_in"))
      (node (ref "U2") (pin "29") (pinfunction "PVDD_29") (pintype "power_in"))
      (node (ref "U2") (pin "30") (pinfunction "PVDD_30") (pintype "power_in"))
      (node (ref "U2") (pin "42") (pinfunction "PVDD_42") (pintype "power_in"))
      (node (ref "U2") (pin "43") (pinfunction "PVDD_43") (pintype "power_in"))
      (node (ref "U2") (pin "55") (pinfunction "PVDD_55") (pintype "power_in"))
      (node (ref "U2") (pin "56") (pinfunction "PVDD_56") (pintype "power_in"))
    )
    (net (code "58") (name "VIN") (class "Default")
      (node (ref "C1") (pin "2") (pinfunction "2_2") (pintype "passive"))
      (node (ref "L1") (pin "2") (pintype "passive"))
      (node (ref "P1") (pin "10") (pinfunction "10_10") (pintype "passive"))
      (node (ref "P1") (pin "12") (pinfunction "12_12") (pintype "passive"))
      (node (ref "P1") (pin "2") (pinfunction "2_2") (pintype "passive"))
      (node (ref "P1") (pin "4") (pinfunction "4_4") (pintype "passive"))
      (node (ref "P1") (pin "6") (pinfunction "6_6") (pintype "passive"))
      (node (ref "P1") (pin "8") (pinfunction "8_8") (pintype "passive"))
      (node (ref "Q1") (pin "3") (pinfunction "S_3") (pintype "passive"))
      (node (ref "R1") (pin "1") (pinfunction "1_1") (pintype "passive"))
    )
  )
)
